# Display_v5.net
KiCad netlist of a schematic drawn in EAGLE
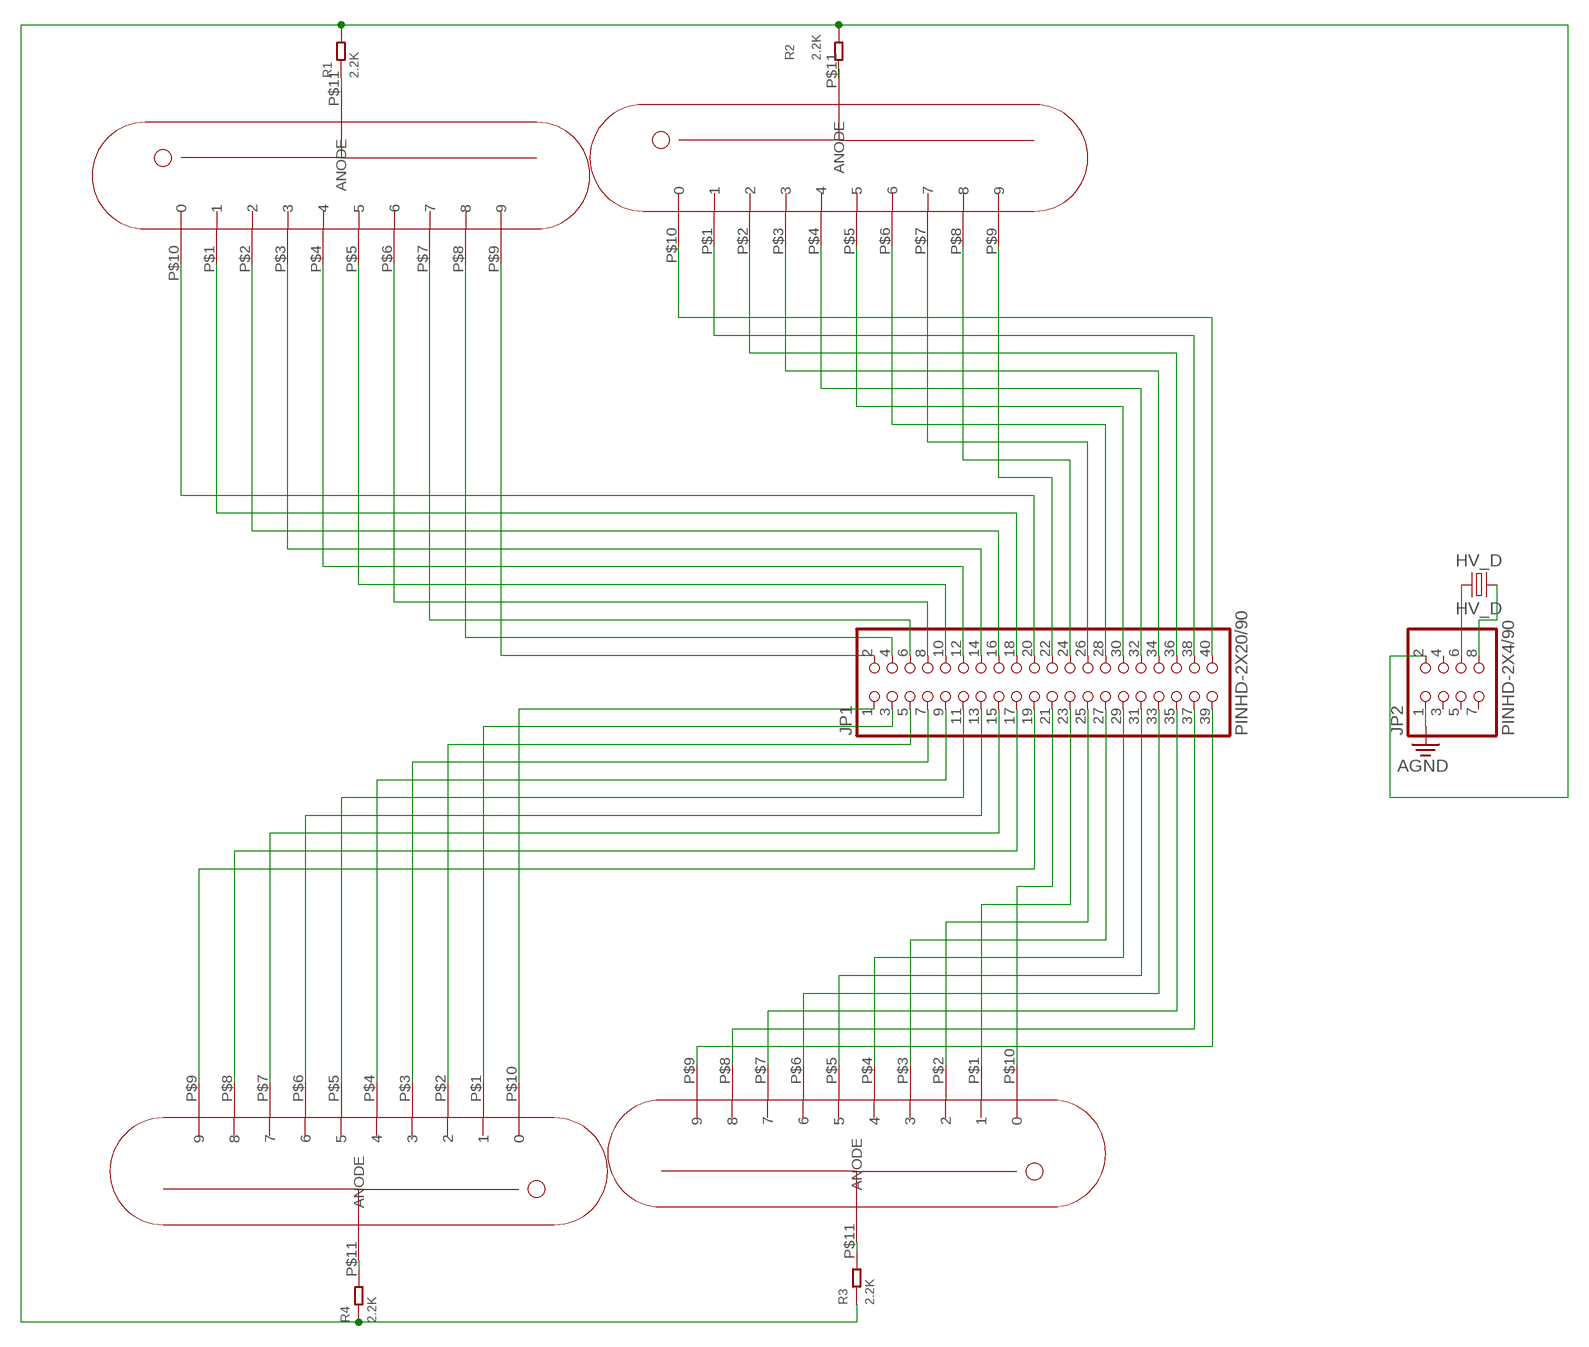
[diagram p0: schematic, sheet 1]

(export (version "E")
  (design (tool "Eeschema 10.0.6"))
  (components
    (comp (ref "HV_D")
      (value "HV_D")
      (footprint "eagle-import:XTALRR488W43L1135T465H1346B")
      (libsource (lib "eagle-import") (part "CRYSTALHC49-11L-13.5H_"))
    )
    (comp (ref "JP1")
      (value "PINHD-2X20/90")
      (footprint "eagle-import:2X20_90")
      (fields (field (name "MANUFACTURER") "Generic"))
      (libsource (lib "eagle-import") (part "PINHD-2X20/90"))
    )
    (comp (ref "JP2")
      (value "PINHD-2X4/90")
      (footprint "eagle-import:2X04_90")
      (fields (field (name "MANUFACTURER") "Generic"))
      (libsource (lib "eagle-import") (part "PINHD-2X4/90"))
    )
    (comp (ref "R1")
      (value "2.2K")
      (footprint "eagle-import:PR-D2.3XL6.5MM")
      (fields (field (name "MPN") "FHCFR-1/4W-222J"))
      (libsource (lib "eagle-import") (part "DIP-RES-2.2K-5%-1/4W(PR-D2.3XL6.5MM)"))
    )
    (comp (ref "R2")
      (value "2.2K")
      (footprint "eagle-import:PR-D2.3XL6.5MM")
      (fields (field (name "MPN") "FHCFR-1/4W-222J"))
      (libsource (lib "eagle-import") (part "DIP-RES-2.2K-5%-1/4W(PR-D2.3XL6.5MM)"))
    )
    (comp (ref "R3")
      (value "2.2K")
      (footprint "eagle-import:PR-D2.3XL6.5MM")
      (fields (field (name "MPN") "FHCFR-1/4W-222J"))
      (libsource (lib "eagle-import") (part "DIP-RES-2.2K-5%-1/4W(PR-D2.3XL6.5MM)"))
    )
    (comp (ref "R4")
      (value "2.2K")
      (footprint "eagle-import:PR-D2.3XL6.5MM")
      (fields (field (name "MPN") "FHCFR-1/4W-222J"))
      (libsource (lib "eagle-import") (part "DIP-RES-2.2K-5%-1/4W(PR-D2.3XL6.5MM)"))
    )
    (comp (ref "U$1")
      (value "IN-12")
      (footprint "eagle-import:IN-12")
      (libsource (lib "eagle-import") (part "IN-12"))
    )
    (comp (ref "U$2")
      (value "IN-12")
      (footprint "eagle-import:IN-12")
      (libsource (lib "eagle-import") (part "IN-12"))
    )
    (comp (ref "U$3")
      (value "IN-12")
      (footprint "eagle-import:IN-12")
      (libsource (lib "eagle-import") (part "IN-12"))
    )
    (comp (ref "U$4")
      (value "IN-12")
      (footprint "eagle-import:IN-12")
      (libsource (lib "eagle-import") (part "IN-12"))
    )
  )
  (nets
    (net (code "1") (name "AGND") (class "Default")
      (node (ref "JP2") (pin "1") (pinfunction "1_1") (pintype "passive"))
    )
    (net (code "2") (name "Net-(HV_D-Pad1)") (class "Default")
      (node (ref "HV_D") (pin "1") (pinfunction "1_1") (pintype "passive"))
      (node (ref "JP2") (pin "6") (pinfunction "6_6") (pintype "passive"))
    )
    (net (code "3") (name "Net-(HV_D-Pad2)") (class "Default")
      (node (ref "HV_D") (pin "2") (pinfunction "2_2") (pintype "passive"))
      (node (ref "JP2") (pin "8") (pinfunction "8_8") (pintype "passive"))
    )
    (net (code "4") (name "Net-(JP2-Pad2)") (class "Default")
      (node (ref "JP2") (pin "2") (pinfunction "2_2") (pintype "passive"))
      (node (ref "R1") (pin "2") (pinfunction "2_2") (pintype "passive"))
      (node (ref "R2") (pin "2") (pinfunction "2_2") (pintype "passive"))
      (node (ref "R3") (pin "1") (pinfunction "1_1") (pintype "passive"))
      (node (ref "R4") (pin "1") (pinfunction "1_1") (pintype "passive"))
    )
    (net (code "5") (name "Net-(U$1-0)") (class "Default")
      (node (ref "JP1") (pin "20") (pinfunction "20_20") (pintype "passive"))
      (node (ref "U$1") (pin "P$10") (pinfunction "0_P$10") (pintype "bidirectional"))
    )
    (net (code "6") (name "Net-(U$1-1)") (class "Default")
      (node (ref "JP1") (pin "18") (pinfunction "18_18") (pintype "passive"))
      (node (ref "U$1") (pin "P$1") (pinfunction "1_P$1") (pintype "bidirectional"))
    )
    (net (code "7") (name "Net-(U$1-2)") (class "Default")
      (node (ref "JP1") (pin "16") (pinfunction "16_16") (pintype "passive"))
      (node (ref "U$1") (pin "P$2") (pinfunction "2_P$2") (pintype "bidirectional"))
    )
    (net (code "8") (name "Net-(U$1-3)") (class "Default")
      (node (ref "JP1") (pin "14") (pinfunction "14_14") (pintype "passive"))
      (node (ref "U$1") (pin "P$3") (pinfunction "3_P$3") (pintype "bidirectional"))
    )
    (net (code "9") (name "Net-(U$1-4)") (class "Default")
      (node (ref "JP1") (pin "12") (pinfunction "12_12") (pintype "passive"))
      (node (ref "U$1") (pin "P$4") (pinfunction "4_P$4") (pintype "bidirectional"))
    )
    (net (code "10") (name "Net-(U$1-5)") (class "Default")
      (node (ref "JP1") (pin "10") (pinfunction "10_10") (pintype "passive"))
      (node (ref "U$1") (pin "P$5") (pinfunction "5_P$5") (pintype "bidirectional"))
    )
    (net (code "11") (name "Net-(U$1-6)") (class "Default")
      (node (ref "JP1") (pin "8") (pinfunction "8_8") (pintype "passive"))
      (node (ref "U$1") (pin "P$6") (pinfunction "6_P$6") (pintype "bidirectional"))
    )
    (net (code "12") (name "Net-(U$1-7)") (class "Default")
      (node (ref "JP1") (pin "6") (pinfunction "6_6") (pintype "passive"))
      (node (ref "U$1") (pin "P$7") (pinfunction "7_P$7") (pintype "bidirectional"))
    )
    (net (code "13") (name "Net-(U$1-8)") (class "Default")
      (node (ref "JP1") (pin "4") (pinfunction "4_4") (pintype "passive"))
      (node (ref "U$1") (pin "P$8") (pinfunction "8_P$8") (pintype "bidirectional"))
    )
    (net (code "14") (name "Net-(U$1-9)") (class "Default")
      (node (ref "JP1") (pin "2") (pinfunction "2_2") (pintype "passive"))
      (node (ref "U$1") (pin "P$9") (pinfunction "9_P$9") (pintype "bidirectional"))
    )
    (net (code "15") (name "Net-(U$1-ANODE)") (class "Default")
      (node (ref "R1") (pin "1") (pinfunction "1_1") (pintype "passive"))
      (node (ref "U$1") (pin "P$11") (pinfunction "ANODE_P$11") (pintype "bidirectional"))
    )
    (net (code "16") (name "Net-(U$2-0)") (class "Default")
      (node (ref "JP1") (pin "40") (pinfunction "40_40") (pintype "passive"))
      (node (ref "U$2") (pin "P$10") (pinfunction "0_P$10") (pintype "bidirectional"))
    )
    (net (code "17") (name "Net-(U$2-1)") (class "Default")
      (node (ref "JP1") (pin "38") (pinfunction "38_38") (pintype "passive"))
      (node (ref "U$2") (pin "P$1") (pinfunction "1_P$1") (pintype "bidirectional"))
    )
    (net (code "18") (name "Net-(U$2-2)") (class "Default")
      (node (ref "JP1") (pin "36") (pinfunction "36_36") (pintype "passive"))
      (node (ref "U$2") (pin "P$2") (pinfunction "2_P$2") (pintype "bidirectional"))
    )
    (net (code "19") (name "Net-(U$2-3)") (class "Default")
      (node (ref "JP1") (pin "34") (pinfunction "34_34") (pintype "passive"))
      (node (ref "U$2") (pin "P$3") (pinfunction "3_P$3") (pintype "bidirectional"))
    )
    (net (code "20") (name "Net-(U$2-4)") (class "Default")
      (node (ref "JP1") (pin "32") (pinfunction "32_32") (pintype "passive"))
      (node (ref "U$2") (pin "P$4") (pinfunction "4_P$4") (pintype "bidirectional"))
    )
    (net (code "21") (name "Net-(U$2-5)") (class "Default")
      (node (ref "JP1") (pin "30") (pinfunction "30_30") (pintype "passive"))
      (node (ref "U$2") (pin "P$5") (pinfunction "5_P$5") (pintype "bidirectional"))
    )
    (net (code "22") (name "Net-(U$2-6)") (class "Default")
      (node (ref "JP1") (pin "28") (pinfunction "28_28") (pintype "passive"))
      (node (ref "U$2") (pin "P$6") (pinfunction "6_P$6") (pintype "bidirectional"))
    )
    (net (code "23") (name "Net-(U$2-7)") (class "Default")
      (node (ref "JP1") (pin "26") (pinfunction "26_26") (pintype "passive"))
      (node (ref "U$2") (pin "P$7") (pinfunction "7_P$7") (pintype "bidirectional"))
    )
    (net (code "24") (name "Net-(U$2-8)") (class "Default")
      (node (ref "JP1") (pin "24") (pinfunction "24_24") (pintype "passive"))
      (node (ref "U$2") (pin "P$8") (pinfunction "8_P$8") (pintype "bidirectional"))
    )
    (net (code "25") (name "Net-(U$2-9)") (class "Default")
      (node (ref "JP1") (pin "22") (pinfunction "22_22") (pintype "passive"))
      (node (ref "U$2") (pin "P$9") (pinfunction "9_P$9") (pintype "bidirectional"))
    )
    (net (code "26") (name "Net-(U$2-ANODE)") (class "Default")
      (node (ref "R2") (pin "1") (pinfunction "1_1") (pintype "passive"))
      (node (ref "U$2") (pin "P$11") (pinfunction "ANODE_P$11") (pintype "bidirectional"))
    )
    (net (code "27") (name "Net-(U$3-0)") (class "Default")
      (node (ref "JP1") (pin "1") (pinfunction "1_1") (pintype "passive"))
      (node (ref "U$3") (pin "P$10") (pinfunction "0_P$10") (pintype "bidirectional"))
    )
    (net (code "28") (name "Net-(U$3-1)") (class "Default")
      (node (ref "JP1") (pin "3") (pinfunction "3_3") (pintype "passive"))
      (node (ref "U$3") (pin "P$1") (pinfunction "1_P$1") (pintype "bidirectional"))
    )
    (net (code "29") (name "Net-(U$3-2)") (class "Default")
      (node (ref "JP1") (pin "5") (pinfunction "5_5") (pintype "passive"))
      (node (ref "U$3") (pin "P$2") (pinfunction "2_P$2") (pintype "bidirectional"))
    )
    (net (code "30") (name "Net-(U$3-3)") (class "Default")
      (node (ref "JP1") (pin "7") (pinfunction "7_7") (pintype "passive"))
      (node (ref "U$3") (pin "P$3") (pinfunction "3_P$3") (pintype "bidirectional"))
    )
    (net (code "31") (name "Net-(U$3-4)") (class "Default")
      (node (ref "JP1") (pin "9") (pinfunction "9_9") (pintype "passive"))
      (node (ref "U$3") (pin "P$4") (pinfunction "4_P$4") (pintype "bidirectional"))
    )
    (net (code "32") (name "Net-(U$3-5)") (class "Default")
      (node (ref "JP1") (pin "11") (pinfunction "11_11") (pintype "passive"))
      (node (ref "U$3") (pin "P$5") (pinfunction "5_P$5") (pintype "bidirectional"))
    )
    (net (code "33") (name "Net-(U$3-6)") (class "Default")
      (node (ref "JP1") (pin "13") (pinfunction "13_13") (pintype "passive"))
      (node (ref "U$3") (pin "P$6") (pinfunction "6_P$6") (pintype "bidirectional"))
    )
    (net (code "34") (name "Net-(U$3-7)") (class "Default")
      (node (ref "JP1") (pin "15") (pinfunction "15_15") (pintype "passive"))
      (node (ref "U$3") (pin "P$7") (pinfunction "7_P$7") (pintype "bidirectional"))
    )
    (net (code "35") (name "Net-(U$3-8)") (class "Default")
      (node (ref "JP1") (pin "17") (pinfunction "17_17") (pintype "passive"))
      (node (ref "U$3") (pin "P$8") (pinfunction "8_P$8") (pintype "bidirectional"))
    )
    (net (code "36") (name "Net-(U$3-9)") (class "Default")
      (node (ref "JP1") (pin "19") (pinfunction "19_19") (pintype "passive"))
      (node (ref "U$3") (pin "P$9") (pinfunction "9_P$9") (pintype "bidirectional"))
    )
    (net (code "37") (name "Net-(U$3-ANODE)") (class "Default")
      (node (ref "R4") (pin "2") (pinfunction "2_2") (pintype "passive"))
      (node (ref "U$3") (pin "P$11") (pinfunction "ANODE_P$11") (pintype "bidirectional"))
    )
    (net (code "38") (name "Net-(U$4-0)") (class "Default")
      (node (ref "JP1") (pin "21") (pinfunction "21_21") (pintype "passive"))
      (node (ref "U$4") (pin "P$10") (pinfunction "0_P$10") (pintype "bidirectional"))
    )
    (net (code "39") (name "Net-(U$4-1)") (class "Default")
      (node (ref "JP1") (pin "23") (pinfunction "23_23") (pintype "passive"))
      (node (ref "U$4") (pin "P$1") (pinfunction "1_P$1") (pintype "bidirectional"))
    )
    (net (code "40") (name "Net-(U$4-2)") (class "Default")
      (node (ref "JP1") (pin "25") (pinfunction "25_25") (pintype "passive"))
      (node (ref "U$4") (pin "P$2") (pinfunction "2_P$2") (pintype "bidirectional"))
    )
    (net (code "41") (name "Net-(U$4-3)") (class "Default")
      (node (ref "JP1") (pin "27") (pinfunction "27_27") (pintype "passive"))
      (node (ref "U$4") (pin "P$3") (pinfunction "3_P$3") (pintype "bidirectional"))
    )
    (net (code "42") (name "Net-(U$4-4)") (class "Default")
      (node (ref "JP1") (pin "29") (pinfunction "29_29") (pintype "passive"))
      (node (ref "U$4") (pin "P$4") (pinfunction "4_P$4") (pintype "bidirectional"))
    )
    (net (code "43") (name "Net-(U$4-5)") (class "Default")
      (node (ref "JP1") (pin "31") (pinfunction "31_31") (pintype "passive"))
      (node (ref "U$4") (pin "P$5") (pinfunction "5_P$5") (pintype "bidirectional"))
    )
    (net (code "44") (name "Net-(U$4-6)") (class "Default")
      (node (ref "JP1") (pin "33") (pinfunction "33_33") (pintype "passive"))
      (node (ref "U$4") (pin "P$6") (pinfunction "6_P$6") (pintype "bidirectional"))
    )
    (net (code "45") (name "Net-(U$4-7)") (class "Default")
      (node (ref "JP1") (pin "35") (pinfunction "35_35") (pintype "passive"))
      (node (ref "U$4") (pin "P$7") (pinfunction "7_P$7") (pintype "bidirectional"))
    )
    (net (code "46") (name "Net-(U$4-8)") (class "Default")
      (node (ref "JP1") (pin "37") (pinfunction "37_37") (pintype "passive"))
      (node (ref "U$4") (pin "P$8") (pinfunction "8_P$8") (pintype "bidirectional"))
    )
    (net (code "47") (name "Net-(U$4-9)") (class "Default")
      (node (ref "JP1") (pin "39") (pinfunction "39_39") (pintype "passive"))
      (node (ref "U$4") (pin "P$9") (pinfunction "9_P$9") (pintype "bidirectional"))
    )
    (net (code "48") (name "Net-(U$4-ANODE)") (class "Default")
      (node (ref "R3") (pin "2") (pinfunction "2_2") (pintype "passive"))
      (node (ref "U$4") (pin "P$11") (pinfunction "ANODE_P$11") (pintype "bidirectional"))
    )
    (net (code "49") (name "unconnected-(JP2-Pad3)") (class "Default")
      (node (ref "JP2") (pin "3") (pinfunction "3_3") (pintype "passive"))
    )
    (net (code "50") (name "unconnected-(JP2-Pad4)") (class "Default")
      (node (ref "JP2") (pin "4") (pinfunction "4_4") (pintype "passive"))
    )
    (net (code "51") (name "unconnected-(JP2-Pad5)") (class "Default")
      (node (ref "JP2") (pin "5") (pinfunction "5_5") (pintype "passive"))
    )
    (net (code "52") (name "unconnected-(JP2-Pad7)") (class "Default")
      (node (ref "JP2") (pin "7") (pinfunction "7_7") (pintype "passive"))
    )
  )
)
